# T11-MIDITheremin.net
KiCad netlist of a schematic drawn in EAGLE
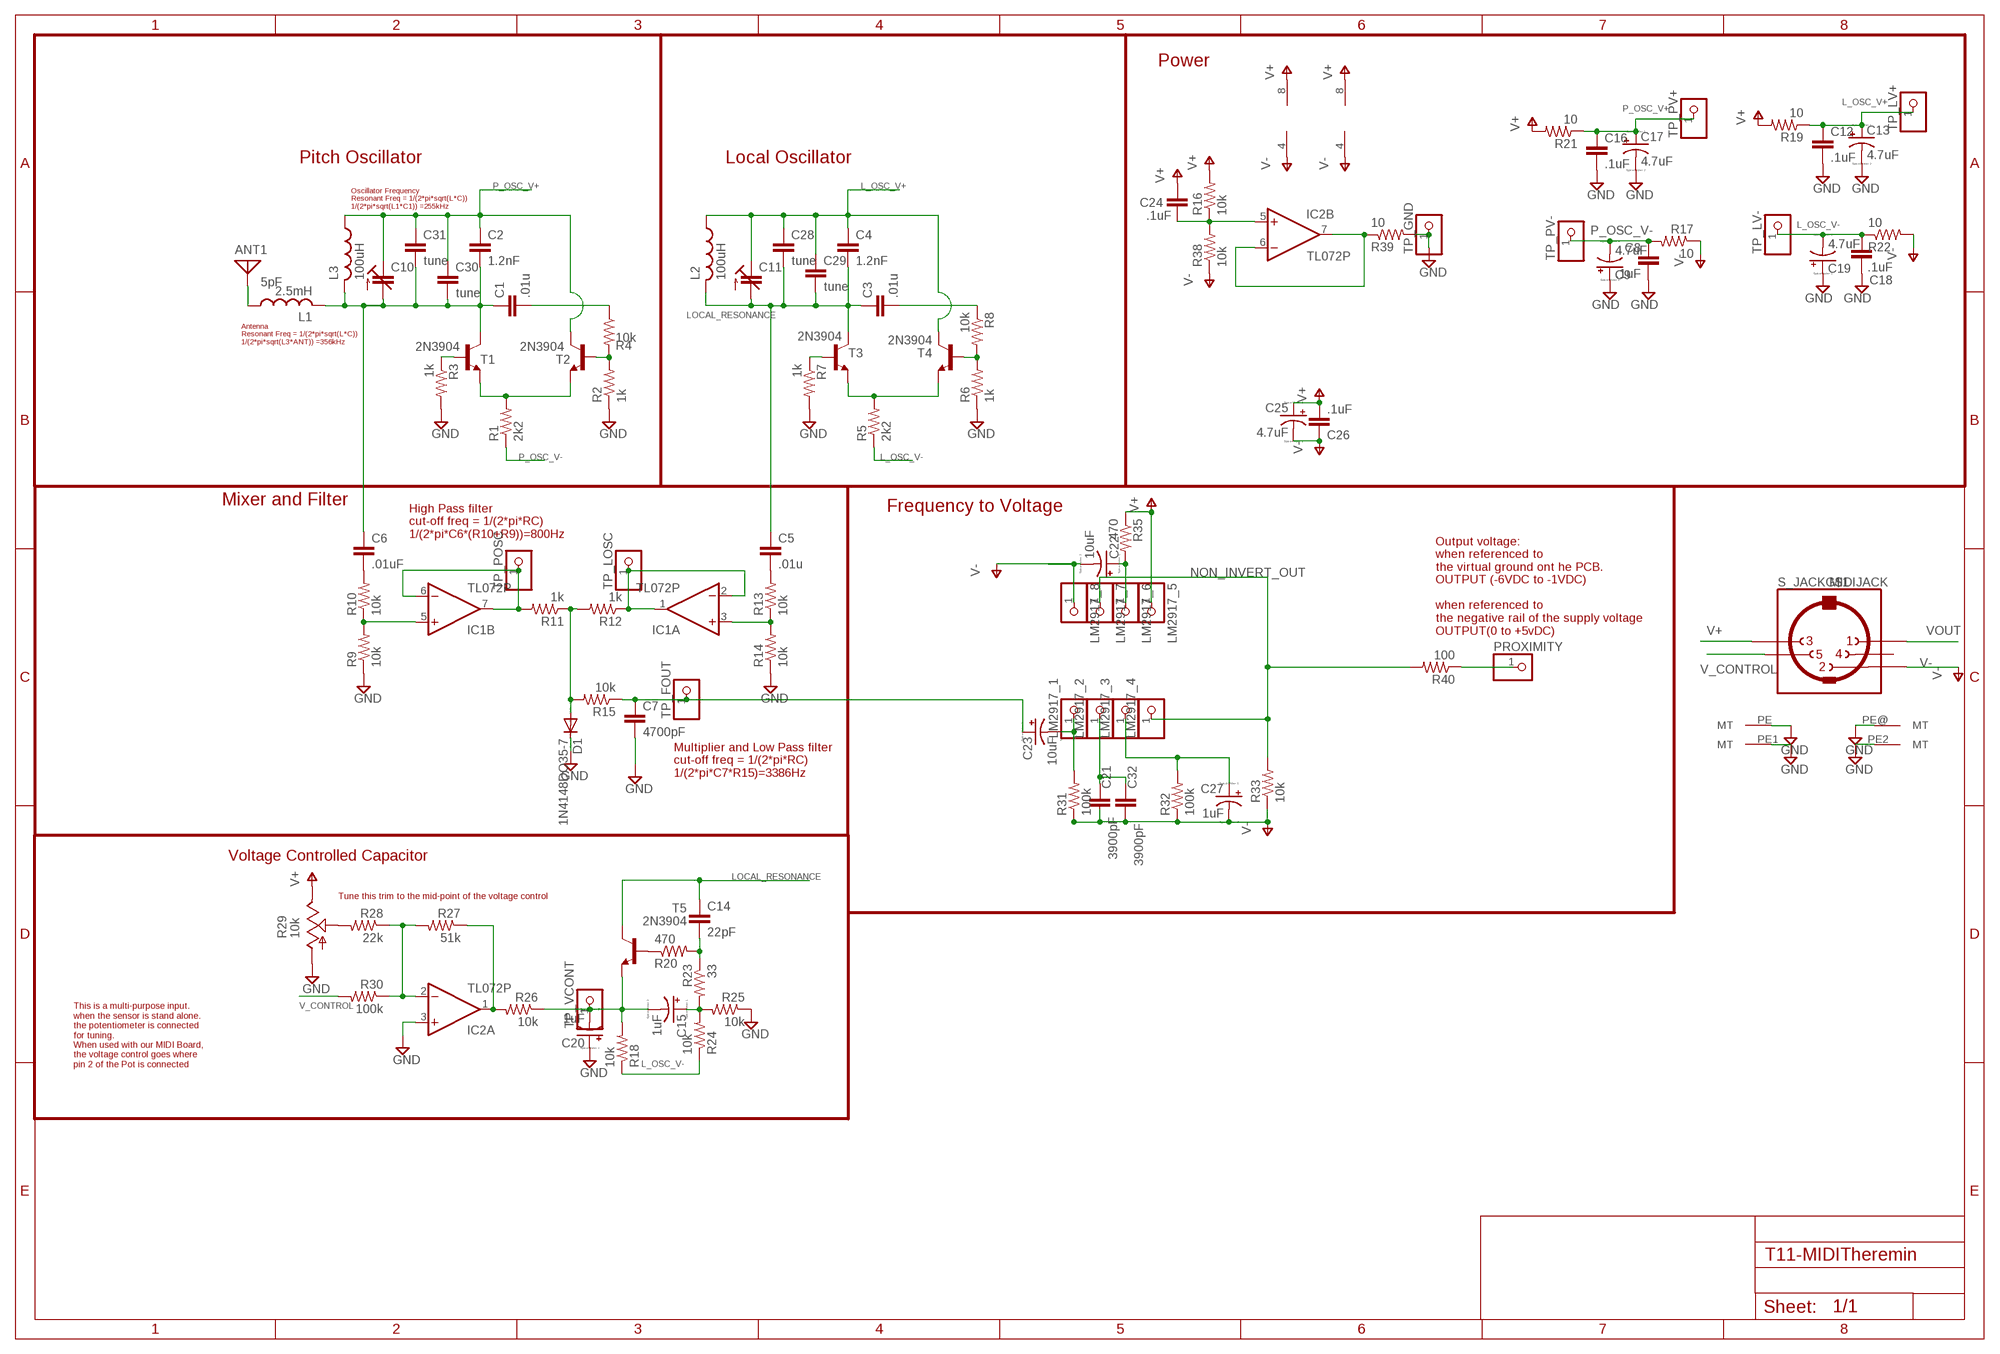
[diagram p0: schematic, sheet 1]

(export (version "E")
  (design (tool "Eeschema 10.0.6"))
  (components
    (comp (ref "ANT1")
      (value "5pF")
      (footprint "eagle-import:PAD-01")
      (libsource (lib "eagle-import") (part "ANTENNA"))
    )
    (comp (ref "C1")
      (value ".01u")
      (footprint "eagle-import:C050-025X075")
      (libsource (lib "eagle-import") (part "C-EU050-025X075"))
    )
    (comp (ref "C2")
      (value "1.2nF")
      (footprint "eagle-import:C050-025X075")
      (libsource (lib "eagle-import") (part "C-EU050-025X075"))
    )
    (comp (ref "C3")
      (value ".01u")
      (footprint "eagle-import:C050-025X075")
      (libsource (lib "eagle-import") (part "C-EU050-025X075"))
    )
    (comp (ref "C4")
      (value "1.2nF")
      (footprint "eagle-import:C050-025X075")
      (libsource (lib "eagle-import") (part "C-EU050-025X075"))
    )
    (comp (ref "C5")
      (value ".01u")
      (footprint "eagle-import:C050-025X075")
      (libsource (lib "eagle-import") (part "C-EU050-025X075"))
    )
    (comp (ref "C6")
      (value ".01uF")
      (footprint "eagle-import:C050-025X075")
      (libsource (lib "eagle-import") (part "C-EU050-025X075"))
    )
    (comp (ref "C7")
      (value "4700pF")
      (footprint "eagle-import:C050-025X075")
      (libsource (lib "eagle-import") (part "C-EU050-025X075"))
    )
    (comp (ref "C8")
      (value ".1uF")
      (footprint "eagle-import:C050-025X075")
      (libsource (lib "eagle-import") (part "C-EU050-025X075"))
    )
    (comp (ref "C9")
      (value "4.7uF")
      (footprint "eagle-import:E2,5-7")
      (libsource (lib "eagle-import") (part "CPOL-USE2.5-7"))
    )
    (comp (ref "C10")
      (value "C-TRIMM3040.427")
      (footprint "eagle-import:CTRIM3040.427")
      (libsource (lib "eagle-import") (part "C-TRIMM3040.427"))
    )
    (comp (ref "C11")
      (value "C-TRIMM3040.427")
      (footprint "eagle-import:CTRIM3040.427")
      (libsource (lib "eagle-import") (part "C-TRIMM3040.427"))
    )
    (comp (ref "C12")
      (value ".1uF")
      (footprint "eagle-import:C050-025X075")
      (libsource (lib "eagle-import") (part "C-EU050-025X075"))
    )
    (comp (ref "C13")
      (value "4.7uF")
      (footprint "eagle-import:E2,5-7")
      (libsource (lib "eagle-import") (part "CPOL-USE2.5-7"))
    )
    (comp (ref "C14")
      (value "22pF")
      (footprint "eagle-import:C050-025X075")
      (libsource (lib "eagle-import") (part "C-EU050-025X075"))
    )
    (comp (ref "C15")
      (value "1uF")
      (footprint "eagle-import:E2,5-7")
      (libsource (lib "eagle-import") (part "CPOL-USE2.5-7"))
    )
    (comp (ref "C16")
      (value ".1uF")
      (footprint "eagle-import:C050-025X075")
      (libsource (lib "eagle-import") (part "C-EU050-025X075"))
    )
    (comp (ref "C17")
      (value "4.7uF")
      (footprint "eagle-import:E2,5-7")
      (libsource (lib "eagle-import") (part "CPOL-USE2.5-7"))
    )
    (comp (ref "C18")
      (value ".1uF")
      (footprint "eagle-import:C050-025X075")
      (libsource (lib "eagle-import") (part "C-EU050-025X075"))
    )
    (comp (ref "C19")
      (value "4.7uF")
      (footprint "eagle-import:E2,5-7")
      (libsource (lib "eagle-import") (part "CPOL-USE2.5-7"))
    )
    (comp (ref "C20")
      (value "1uF")
      (footprint "eagle-import:E2,5-7")
      (libsource (lib "eagle-import") (part "CPOL-USE2.5-7"))
    )
    (comp (ref "C21")
      (value "3900pF")
      (footprint "eagle-import:C050-025X075")
      (libsource (lib "eagle-import") (part "C-EU050-025X075"))
    )
    (comp (ref "C22")
      (value "10uF")
      (footprint "eagle-import:E2,5-7")
      (libsource (lib "eagle-import") (part "CPOL-USE2.5-7"))
    )
    (comp (ref "C23")
      (value "10uF")
      (footprint "eagle-import:E2,5-7")
      (libsource (lib "eagle-import") (part "CPOL-USE2.5-7"))
    )
    (comp (ref "C24")
      (value ".1uF")
      (footprint "eagle-import:C050-025X075")
      (libsource (lib "eagle-import") (part "C-EU050-025X075"))
    )
    (comp (ref "C25")
      (value "4.7uF")
      (footprint "eagle-import:E2,5-7")
      (libsource (lib "eagle-import") (part "CPOL-USE2.5-7"))
    )
    (comp (ref "C26")
      (value ".1uF")
      (footprint "eagle-import:C050-025X075")
      (libsource (lib "eagle-import") (part "C-EU050-025X075"))
    )
    (comp (ref "C27")
      (value "1uF")
      (footprint "eagle-import:E2,5-7")
      (libsource (lib "eagle-import") (part "CPOL-USE2.5-7"))
    )
    (comp (ref "C28")
      (value "tune")
      (footprint "eagle-import:C050-025X075")
      (libsource (lib "eagle-import") (part "C-EU050-025X075"))
    )
    (comp (ref "C29")
      (value "tune")
      (footprint "eagle-import:C050-025X075")
      (libsource (lib "eagle-import") (part "C-EU050-025X075"))
    )
    (comp (ref "C30")
      (value "tune")
      (footprint "eagle-import:C050-025X075")
      (libsource (lib "eagle-import") (part "C-EU050-025X075"))
    )
    (comp (ref "C31")
      (value "tune")
      (footprint "eagle-import:C050-025X075")
      (libsource (lib "eagle-import") (part "C-EU050-025X075"))
    )
    (comp (ref "C32")
      (value "3900pF")
      (footprint "eagle-import:C050-025X075")
      (libsource (lib "eagle-import") (part "C-EU050-025X075"))
    )
    (comp (ref "D1")
      (value "1N4148DO35-7")
      (footprint "eagle-import:DO35-7")
      (libsource (lib "eagle-import") (part "1N4148DO35-7"))
    )
    (comp (ref "IC1")
      (value "TL072P")
      (footprint "eagle-import:DIL08")
      (libsource (lib "eagle-import") (part "TL072P"))
    )
    (comp (ref "IC2")
      (value "TL072P")
      (footprint "eagle-import:DIL08")
      (libsource (lib "eagle-import") (part "TL072P"))
    )
    (comp (ref "L1")
      (value "2.5mH")
      (footprint "eagle-import:0207_5V")
      (libsource (lib "eagle-import") (part "L-US0207/5V"))
    )
    (comp (ref "L2")
      (value "100uH")
      (footprint "eagle-import:0207_5V")
      (libsource (lib "eagle-import") (part "L-US0207/5V"))
    )
    (comp (ref "L3")
      (value "100uH")
      (footprint "eagle-import:0207_5V")
      (libsource (lib "eagle-import") (part "L-US0207/5V"))
    )
    (comp (ref "LM2917_1")
      (value "PINHD-1X1")
      (footprint "eagle-import:1X01")
      (libsource (lib "eagle-import") (part "PINHD-1X1"))
    )
    (comp (ref "LM2917_2")
      (value "PINHD-1X1")
      (footprint "eagle-import:1X01")
      (libsource (lib "eagle-import") (part "PINHD-1X1"))
    )
    (comp (ref "LM2917_3")
      (value "PINHD-1X1")
      (footprint "eagle-import:1X01")
      (libsource (lib "eagle-import") (part "PINHD-1X1"))
    )
    (comp (ref "LM2917_4")
      (value "PINHD-1X1")
      (footprint "eagle-import:1X01")
      (libsource (lib "eagle-import") (part "PINHD-1X1"))
    )
    (comp (ref "LM2917_5")
      (value "PINHD-1X1")
      (footprint "eagle-import:1X01")
      (libsource (lib "eagle-import") (part "PINHD-1X1"))
    )
    (comp (ref "LM2917_6")
      (value "PINHD-1X1")
      (footprint "eagle-import:1X01")
      (libsource (lib "eagle-import") (part "PINHD-1X1"))
    )
    (comp (ref "LM2917_7")
      (value "PINHD-1X1")
      (footprint "eagle-import:1X01")
      (libsource (lib "eagle-import") (part "PINHD-1X1"))
    )
    (comp (ref "LM2917_8")
      (value "PINHD-1X1")
      (footprint "eagle-import:1X01")
      (libsource (lib "eagle-import") (part "PINHD-1X1"))
    )
    (comp (ref "PROXIMITY")
      (value "PINHD-1X1")
      (footprint "eagle-import:1X01")
      (libsource (lib "eagle-import") (part "PINHD-1X1"))
    )
    (comp (ref "R1")
      (value "2k2")
      (footprint "eagle-import:0411V")
      (libsource (lib "eagle-import") (part "resistor_R-US_0411/3V"))
    )
    (comp (ref "R2")
      (value "1k")
      (footprint "eagle-import:0411V")
      (libsource (lib "eagle-import") (part "resistor_R-US_0411/3V"))
    )
    (comp (ref "R3")
      (value "1k")
      (footprint "eagle-import:0411V")
      (libsource (lib "eagle-import") (part "resistor_R-US_0411/3V"))
    )
    (comp (ref "R4")
      (value "10k")
      (footprint "eagle-import:0411V")
      (libsource (lib "eagle-import") (part "resistor_R-US_0411/3V"))
    )
    (comp (ref "R5")
      (value "2k2")
      (footprint "eagle-import:0411V")
      (libsource (lib "eagle-import") (part "resistor_R-US_0411/3V"))
    )
    (comp (ref "R6")
      (value "1k")
      (footprint "eagle-import:0411V")
      (libsource (lib "eagle-import") (part "resistor_R-US_0411/3V"))
    )
    (comp (ref "R7")
      (value "1k")
      (footprint "eagle-import:0411V")
      (libsource (lib "eagle-import") (part "resistor_R-US_0411/3V"))
    )
    (comp (ref "R8")
      (value "10k")
      (footprint "eagle-import:0411V")
      (libsource (lib "eagle-import") (part "resistor_R-US_0411/3V"))
    )
    (comp (ref "R9")
      (value "10k")
      (footprint "eagle-import:0411V")
      (libsource (lib "eagle-import") (part "resistor_R-US_0411/3V"))
    )
    (comp (ref "R10")
      (value "10k")
      (footprint "eagle-import:0411V")
      (libsource (lib "eagle-import") (part "resistor_R-US_0411/3V"))
    )
    (comp (ref "R11")
      (value "1k")
      (footprint "eagle-import:0411V")
      (libsource (lib "eagle-import") (part "resistor_R-US_0411/3V"))
    )
    (comp (ref "R12")
      (value "1k")
      (footprint "eagle-import:0411V")
      (libsource (lib "eagle-import") (part "resistor_R-US_0411/3V"))
    )
    (comp (ref "R13")
      (value "10k")
      (footprint "eagle-import:0411V")
      (libsource (lib "eagle-import") (part "resistor_R-US_0411/3V"))
    )
    (comp (ref "R14")
      (value "10k")
      (footprint "eagle-import:0411V")
      (libsource (lib "eagle-import") (part "resistor_R-US_0411/3V"))
    )
    (comp (ref "R15")
      (value "10k")
      (footprint "eagle-import:0411V")
      (libsource (lib "eagle-import") (part "resistor_R-US_0411/3V"))
    )
    (comp (ref "R16")
      (value "10k")
      (footprint "eagle-import:0411V")
      (libsource (lib "eagle-import") (part "resistor_R-US_0411/3V"))
    )
    (comp (ref "R17")
      (value "10")
      (footprint "eagle-import:0411V")
      (libsource (lib "eagle-import") (part "resistor_R-US_0411/3V"))
    )
    (comp (ref "R18")
      (value "10k")
      (footprint "eagle-import:0411V")
      (libsource (lib "eagle-import") (part "resistor_R-US_0411/3V"))
    )
    (comp (ref "R19")
      (value "10")
      (footprint "eagle-import:0411V")
      (libsource (lib "eagle-import") (part "resistor_R-US_0411/3V"))
    )
    (comp (ref "R20")
      (value "470")
      (footprint "eagle-import:0411V")
      (libsource (lib "eagle-import") (part "resistor_R-US_0411/3V"))
    )
    (comp (ref "R21")
      (value "10")
      (footprint "eagle-import:0411V")
      (libsource (lib "eagle-import") (part "resistor_R-US_0411/3V"))
    )
    (comp (ref "R22")
      (value "10")
      (footprint "eagle-import:0411V")
      (libsource (lib "eagle-import") (part "resistor_R-US_0411/3V"))
    )
    (comp (ref "R23")
      (value "33")
      (footprint "eagle-import:0411V")
      (libsource (lib "eagle-import") (part "resistor_R-US_0411/3V"))
    )
    (comp (ref "R24")
      (value "10k")
      (footprint "eagle-import:0411V")
      (libsource (lib "eagle-import") (part "resistor_R-US_0411/3V"))
    )
    (comp (ref "R25")
      (value "10k")
      (footprint "eagle-import:0411V")
      (libsource (lib "eagle-import") (part "resistor_R-US_0411/3V"))
    )
    (comp (ref "R26")
      (value "10k")
      (footprint "eagle-import:0411V")
      (libsource (lib "eagle-import") (part "resistor_R-US_0411/3V"))
    )
    (comp (ref "R27")
      (value "51k")
      (footprint "eagle-import:0411V")
      (libsource (lib "eagle-import") (part "resistor_R-US_0411/3V"))
    )
    (comp (ref "R28")
      (value "22k")
      (footprint "eagle-import:0411V")
      (libsource (lib "eagle-import") (part "resistor_R-US_0411/3V"))
    )
    (comp (ref "R29")
      (value "10k")
      (footprint "eagle-import:B64Y")
      (libsource (lib "eagle-import") (part "TRIM_US-B64Y"))
    )
    (comp (ref "R30")
      (value "100k")
      (footprint "eagle-import:0411V")
      (libsource (lib "eagle-import") (part "resistor_R-US_0411/3V"))
    )
    (comp (ref "R31")
      (value "100k")
      (footprint "eagle-import:0411V")
      (libsource (lib "eagle-import") (part "R-US_0411/3V"))
    )
    (comp (ref "R32")
      (value "100k")
      (footprint "eagle-import:0411V")
      (libsource (lib "eagle-import") (part "R-US_0411/3V"))
    )
    (comp (ref "R33")
      (value "10k")
      (footprint "eagle-import:0411V")
      (libsource (lib "eagle-import") (part "R-US_0411/3V"))
    )
    (comp (ref "R35")
      (value "470")
      (footprint "eagle-import:0411V")
      (libsource (lib "eagle-import") (part "R-US_0411/3V"))
    )
    (comp (ref "R38")
      (value "10k")
      (footprint "eagle-import:0411V")
      (libsource (lib "eagle-import") (part "resistor_R-US_0411/3V"))
    )
    (comp (ref "R39")
      (value "10")
      (footprint "eagle-import:0411V")
      (libsource (lib "eagle-import") (part "resistor_R-US_0411/3V"))
    )
    (comp (ref "R40")
      (value "100")
      (footprint "eagle-import:0411V")
      (libsource (lib "eagle-import") (part "R-US_0411/3V"))
    )
    (comp (ref "S_JACK")
      (value "MIDIJACK")
      (footprint "eagle-import:CP-2350")
      (libsource (lib "eagle-import") (part "MIDIJACK"))
    )
    (comp (ref "T1")
      (value "2N3904")
      (footprint "eagle-import:TO92")
      (libsource (lib "eagle-import") (part "2N3904"))
    )
    (comp (ref "T2")
      (value "2N3904")
      (footprint "eagle-import:TO92")
      (libsource (lib "eagle-import") (part "2N3904"))
    )
    (comp (ref "T3")
      (value "2N3904")
      (footprint "eagle-import:TO92")
      (libsource (lib "eagle-import") (part "2N3904"))
    )
    (comp (ref "T4")
      (value "2N3904")
      (footprint "eagle-import:TO92")
      (libsource (lib "eagle-import") (part "2N3904"))
    )
    (comp (ref "T5")
      (value "2N3904")
      (footprint "eagle-import:TO92")
      (libsource (lib "eagle-import") (part "2N3904"))
    )
    (comp (ref "TP_FOUT")
      (value "PINHD-1X1")
      (footprint "eagle-import:1X01")
      (libsource (lib "eagle-import") (part "PINHD-1X1"))
    )
    (comp (ref "TP_GND")
      (value "PINHD-1X1")
      (footprint "eagle-import:1X01")
      (libsource (lib "eagle-import") (part "PINHD-1X1"))
    )
    (comp (ref "TP_LOSC")
      (value "PINHD-1X1")
      (footprint "eagle-import:1X01")
      (libsource (lib "eagle-import") (part "PINHD-1X1"))
    )
    (comp (ref "TP_LV+")
      (value "PINHD-1X1")
      (footprint "eagle-import:1X01")
      (libsource (lib "eagle-import") (part "PINHD-1X1"))
    )
    (comp (ref "TP_LV-")
      (value "PINHD-1X1")
      (footprint "eagle-import:1X01")
      (libsource (lib "eagle-import") (part "PINHD-1X1"))
    )
    (comp (ref "TP_POSC")
      (value "PINHD-1X1")
      (footprint "eagle-import:1X01")
      (libsource (lib "eagle-import") (part "PINHD-1X1"))
    )
    (comp (ref "TP_PV+")
      (value "PINHD-1X1")
      (footprint "eagle-import:1X01")
      (libsource (lib "eagle-import") (part "PINHD-1X1"))
    )
    (comp (ref "TP_PV-")
      (value "PINHD-1X1")
      (footprint "eagle-import:1X01")
      (libsource (lib "eagle-import") (part "PINHD-1X1"))
    )
    (comp (ref "TP_VCONT")
      (value "PINHD-1X1")
      (footprint "eagle-import:1X01")
      (libsource (lib "eagle-import") (part "PINHD-1X1"))
    )
  )
  (nets
    (net (code "1") (name "/LOCAL_RESONANCE") (class "Default")
      (node (ref "C11") (pin "2") (pinfunction "A_2") (pintype "passive"))
      (node (ref "C14") (pin "1") (pinfunction "1_1") (pintype "passive"))
      (node (ref "C28") (pin "2") (pinfunction "2_2") (pintype "passive"))
      (node (ref "C29") (pin "2") (pinfunction "2_2") (pintype "passive"))
      (node (ref "C3") (pin "1") (pinfunction "1_1") (pintype "passive"))
      (node (ref "C4") (pin "2") (pinfunction "2_2") (pintype "passive"))
      (node (ref "C5") (pin "1") (pinfunction "1_1") (pintype "passive"))
      (node (ref "L2") (pin "2") (pinfunction "2_2") (pintype "passive"))
      (node (ref "T3") (pin "1") (pinfunction "C_1") (pintype "passive"))
      (node (ref "T5") (pin "1") (pinfunction "C_1") (pintype "passive"))
    )
    (net (code "2") (name "/L_OSC_V+") (class "Default")
      (node (ref "C11") (pin "1A") (pinfunction "E_1A") (pintype "passive"))
      (node (ref "C12") (pin "1") (pinfunction "1_1") (pintype "passive"))
      (node (ref "C13") (pin "+") (pinfunction "+_+") (pintype "passive"))
      (node (ref "C28") (pin "1") (pinfunction "1_1") (pintype "passive"))
      (node (ref "C29") (pin "1") (pinfunction "1_1") (pintype "passive"))
      (node (ref "C4") (pin "1") (pinfunction "1_1") (pintype "passive"))
      (node (ref "L2") (pin "1") (pinfunction "1_1") (pintype "passive"))
      (node (ref "R19") (pin "1") (pinfunction "1_1") (pintype "passive"))
      (node (ref "T4") (pin "1") (pinfunction "C_1") (pintype "passive"))
      (node (ref "TP_LV+") (pin "1") (pinfunction "1_1") (pintype "passive"))
    )
    (net (code "3") (name "/L_OSC_V-") (class "Default")
      (node (ref "C18") (pin "1") (pinfunction "1_1") (pintype "passive"))
      (node (ref "C19") (pin "-") (pinfunction "-_-") (pintype "passive"))
      (node (ref "R18") (pin "1") (pinfunction "1_1") (pintype "passive"))
      (node (ref "R22") (pin "1") (pinfunction "1_1") (pintype "passive"))
      (node (ref "R24") (pin "1") (pinfunction "1_1") (pintype "passive"))
      (node (ref "R5") (pin "1") (pinfunction "1_1") (pintype "passive"))
      (node (ref "TP_LV-") (pin "1") (pinfunction "1_1") (pintype "passive"))
    )
    (net (code "4") (name "/NON_INVERT_OUT") (class "Default")
      (node (ref "LM2917_4") (pin "1") (pinfunction "1_1") (pintype "passive"))
      (node (ref "LM2917_7") (pin "1") (pinfunction "1_1") (pintype "passive"))
      (node (ref "R33") (pin "2") (pinfunction "2_2") (pintype "passive"))
      (node (ref "R40") (pin "2") (pinfunction "2_2") (pintype "passive"))
    )
    (net (code "5") (name "/P_OSC_V+") (class "Default")
      (node (ref "C10") (pin "1A") (pinfunction "E_1A") (pintype "passive"))
      (node (ref "C16") (pin "1") (pinfunction "1_1") (pintype "passive"))
      (node (ref "C17") (pin "+") (pinfunction "+_+") (pintype "passive"))
      (node (ref "C2") (pin "1") (pinfunction "1_1") (pintype "passive"))
      (node (ref "C30") (pin "1") (pinfunction "1_1") (pintype "passive"))
      (node (ref "C31") (pin "1") (pinfunction "1_1") (pintype "passive"))
      (node (ref "L3") (pin "1") (pinfunction "1_1") (pintype "passive"))
      (node (ref "R21") (pin "1") (pinfunction "1_1") (pintype "passive"))
      (node (ref "T2") (pin "1") (pinfunction "C_1") (pintype "passive"))
      (node (ref "TP_PV+") (pin "1") (pinfunction "1_1") (pintype "passive"))
    )
    (net (code "6") (name "/P_OSC_V-") (class "Default")
      (node (ref "C8") (pin "1") (pinfunction "1_1") (pintype "passive"))
      (node (ref "C9") (pin "-") (pinfunction "-_-") (pintype "passive"))
      (node (ref "R1") (pin "1") (pinfunction "1_1") (pintype "passive"))
      (node (ref "R17") (pin "2") (pinfunction "2_2") (pintype "passive"))
      (node (ref "TP_PV-") (pin "1") (pinfunction "1_1") (pintype "passive"))
    )
    (net (code "7") (name "/VOUT") (class "Default")
      (node (ref "PROXIMITY") (pin "1") (pinfunction "1_1") (pintype "passive"))
      (node (ref "R40") (pin "1") (pinfunction "1_1") (pintype "passive"))
      (node (ref "S_JACK") (pin "1") (pinfunction "1_1") (pintype "passive"))
    )
    (net (code "8") (name "/V_CONTROL") (class "Default")
      (node (ref "R30") (pin "2") (pinfunction "2_2") (pintype "passive"))
      (node (ref "S_JACK") (pin "5") (pinfunction "5_5") (pintype "passive"))
    )
    (net (code "9") (name "GND") (class "Default")
      (node (ref "C12") (pin "2") (pinfunction "2_2") (pintype "passive"))
      (node (ref "C13") (pin "-") (pinfunction "-_-") (pintype "passive"))
      (node (ref "C16") (pin "2") (pinfunction "2_2") (pintype "passive"))
      (node (ref "C17") (pin "-") (pinfunction "-_-") (pintype "passive"))
      (node (ref "C18") (pin "2") (pinfunction "2_2") (pintype "passive"))
      (node (ref "C19") (pin "+") (pinfunction "+_+") (pintype "passive"))
      (node (ref "C20") (pin "+") (pinfunction "+_+") (pintype "passive"))
      (node (ref "C7") (pin "2") (pinfunction "2_2") (pintype "passive"))
      (node (ref "C8") (pin "2") (pinfunction "2_2") (pintype "passive"))
      (node (ref "C9") (pin "+") (pinfunction "+_+") (pintype "passive"))
      (node (ref "D1") (pin "C") (pinfunction "C_C") (pintype "passive"))
      (node (ref "IC2") (pin "3") (pinfunction "+IN_3") (pintype "input"))
      (node (ref "R14") (pin "1") (pinfunction "1_1") (pintype "passive"))
      (node (ref "R2") (pin "1") (pinfunction "1_1") (pintype "passive"))
      (node (ref "R25") (pin "1") (pinfunction "1_1") (pintype "passive"))
      (node (ref "R29") (pin "A") (pinfunction "A_A") (pintype "passive"))
      (node (ref "R3") (pin "2") (pinfunction "2_2") (pintype "passive"))
      (node (ref "R39") (pin "2") (pinfunction "2_2") (pintype "passive"))
      (node (ref "R6") (pin "1") (pinfunction "1_1") (pintype "passive"))
      (node (ref "R7") (pin "2") (pinfunction "2_2") (pintype "passive"))
      (node (ref "R9") (pin "1") (pinfunction "1_1") (pintype "passive"))
      (node (ref "S_JACK") (pin "PE") (pinfunction "MT_PE") (pintype "passive"))
      (node (ref "S_JACK") (pin "PE1") (pinfunction "MT_PE1") (pintype "passive"))
      (node (ref "S_JACK") (pin "PE2") (pinfunction "MT_PE2") (pintype "passive"))
      (node (ref "S_JACK") (pin "PE@") (pinfunction "MT_PE@") (pintype "passive"))
      (node (ref "TP_GND") (pin "1") (pinfunction "1_1") (pintype "passive"))
    )
    (net (code "10") (name "Net-(ANT1-Pad1)") (class "Default")
      (node (ref "ANT1") (pin "1") (pinfunction "1_1") (pintype "output"))
      (node (ref "L1") (pin "1") (pinfunction "1_1") (pintype "passive"))
    )
    (net (code "11") (name "Net-(C1-Pad2)") (class "Default")
      (node (ref "C1") (pin "2") (pinfunction "2_2") (pintype "passive"))
      (node (ref "R4") (pin "1") (pinfunction "1_1") (pintype "passive"))
    )
    (net (code "12") (name "Net-(C3-Pad2)") (class "Default")
      (node (ref "C3") (pin "2") (pinfunction "2_2") (pintype "passive"))
      (node (ref "R8") (pin "1") (pinfunction "1_1") (pintype "passive"))
    )
    (net (code "13") (name "Net-(C5-Pad2)") (class "Default")
      (node (ref "C5") (pin "2") (pinfunction "2_2") (pintype "passive"))
      (node (ref "R13") (pin "2") (pinfunction "2_2") (pintype "passive"))
    )
    (net (code "14") (name "Net-(C6-Pad2)") (class "Default")
      (node (ref "C6") (pin "2") (pinfunction "2_2") (pintype "passive"))
      (node (ref "R10") (pin "2") (pinfunction "2_2") (pintype "passive"))
    )
    (net (code "15") (name "Net-(C10-A)") (class "Default")
      (node (ref "C1") (pin "1") (pinfunction "1_1") (pintype "passive"))
      (node (ref "C10") (pin "2") (pinfunction "A_2") (pintype "passive"))
      (node (ref "C2") (pin "2") (pinfunction "2_2") (pintype "passive"))
      (node (ref "C30") (pin "2") (pinfunction "2_2") (pintype "passive"))
      (node (ref "C31") (pin "2") (pinfunction "2_2") (pintype "passive"))
      (node (ref "C6") (pin "1") (pinfunction "1_1") (pintype "passive"))
      (node (ref "L1") (pin "2") (pinfunction "2_2") (pintype "passive"))
      (node (ref "L3") (pin "2") (pinfunction "2_2") (pintype "passive"))
      (node (ref "T1") (pin "1") (pinfunction "C_1") (pintype "passive"))
    )
    (net (code "16") (name "Net-(C14-Pad2)") (class "Default")
      (node (ref "C14") (pin "2") (pinfunction "2_2") (pintype "passive"))
      (node (ref "R20") (pin "2") (pinfunction "2_2") (pintype "passive"))
      (node (ref "R23") (pin "1") (pinfunction "1_1") (pintype "passive"))
    )
    (net (code "17") (name "Net-(C15-Pad+)") (class "Default")
      (node (ref "C15") (pin "+") (pinfunction "+_+") (pintype "passive"))
      (node (ref "R23") (pin "2") (pinfunction "2_2") (pintype "passive"))
      (node (ref "R24") (pin "2") (pinfunction "2_2") (pintype "passive"))
      (node (ref "R25") (pin "2") (pinfunction "2_2") (pintype "passive"))
    )
    (net (code "18") (name "Net-(C21-Pad1)") (class "Default")
      (node (ref "C21") (pin "1") (pinfunction "1_1") (pintype "passive"))
      (node (ref "C32") (pin "1") (pinfunction "1_1") (pintype "passive"))
      (node (ref "LM2917_2") (pin "1") (pinfunction "1_1") (pintype "passive"))
    )
    (net (code "19") (name "Net-(C22-Pad+)") (class "Default")
      (node (ref "C22") (pin "+") (pinfunction "+_+") (pintype "passive"))
      (node (ref "LM2917_6") (pin "1") (pinfunction "1_1") (pintype "passive"))
      (node (ref "R35") (pin "2") (pinfunction "2_2") (pintype "passive"))
    )
    (net (code "20") (name "Net-(C23-Pad+)") (class "Default")
      (node (ref "C23") (pin "+") (pinfunction "+_+") (pintype "passive"))
      (node (ref "C7") (pin "1") (pinfunction "1_1") (pintype "passive"))
      (node (ref "R15") (pin "1") (pinfunction "1_1") (pintype "passive"))
      (node (ref "TP_FOUT") (pin "1") (pinfunction "1_1") (pintype "passive"))
    )
    (net (code "21") (name "Net-(C23-Pad-)") (class "Default")
      (node (ref "C23") (pin "-") (pinfunction "-_-") (pintype "passive"))
      (node (ref "LM2917_1") (pin "1") (pinfunction "1_1") (pintype "passive"))
      (node (ref "R31") (pin "2") (pinfunction "2_2") (pintype "passive"))
    )
    (net (code "22") (name "Net-(C27-Pad+)") (class "Default")
      (node (ref "C27") (pin "+") (pinfunction "+_+") (pintype "passive"))
      (node (ref "LM2917_3") (pin "1") (pinfunction "1_1") (pintype "passive"))
      (node (ref "R32") (pin "2") (pinfunction "2_2") (pintype "passive"))
    )
    (net (code "23") (name "Net-(D1-PadA)") (class "Default")
      (node (ref "D1") (pin "A") (pinfunction "A_A") (pintype "passive"))
      (node (ref "R11") (pin "1") (pinfunction "1_1") (pintype "passive"))
      (node (ref "R12") (pin "2") (pinfunction "2_2") (pintype "passive"))
      (node (ref "R15") (pin "2") (pinfunction "2_2") (pintype "passive"))
    )
    (net (code "24") (name "Net-(IC1A-+IN)") (class "Default")
      (node (ref "IC1") (pin "3") (pinfunction "+IN_3") (pintype "input"))
      (node (ref "R13") (pin "1") (pinfunction "1_1") (pintype "passive"))
      (node (ref "R14") (pin "2") (pinfunction "2_2") (pintype "passive"))
    )
    (net (code "25") (name "Net-(IC1A--IN)") (class "Default")
      (node (ref "IC1") (pin "1") (pinfunction "OUT_1") (pintype "output"))
      (node (ref "IC1") (pin "2") (pinfunction "-IN_2") (pintype "input"))
      (node (ref "R12") (pin "1") (pinfunction "1_1") (pintype "passive"))
      (node (ref "TP_LOSC") (pin "1") (pinfunction "1_1") (pintype "passive"))
    )
    (net (code "26") (name "Net-(IC1B-+IN)") (class "Default")
      (node (ref "IC1") (pin "5") (pinfunction "+IN_5") (pintype "input"))
      (node (ref "R10") (pin "1") (pinfunction "1_1") (pintype "passive"))
      (node (ref "R9") (pin "2") (pinfunction "2_2") (pintype "passive"))
    )
    (net (code "27") (name "Net-(IC1B--IN)") (class "Default")
      (node (ref "IC1") (pin "6") (pinfunction "-IN_6") (pintype "input"))
      (node (ref "IC1") (pin "7") (pinfunction "OUT_7") (pintype "output"))
      (node (ref "R11") (pin "2") (pinfunction "2_2") (pintype "passive"))
      (node (ref "TP_POSC") (pin "1") (pinfunction "1_1") (pintype "passive"))
    )
    (net (code "28") (name "Net-(IC2A--IN)") (class "Default")
      (node (ref "IC2") (pin "2") (pinfunction "-IN_2") (pintype "input"))
      (node (ref "R27") (pin "2") (pinfunction "2_2") (pintype "passive"))
      (node (ref "R28") (pin "1") (pinfunction "1_1") (pintype "passive"))
      (node (ref "R30") (pin "1") (pinfunction "1_1") (pintype "passive"))
    )
    (net (code "29") (name "Net-(IC2A-OUT)") (class "Default")
      (node (ref "IC2") (pin "1") (pinfunction "OUT_1") (pintype "output"))
      (node (ref "R26") (pin "2") (pinfunction "2_2") (pintype "passive"))
      (node (ref "R27") (pin "1") (pinfunction "1_1") (pintype "passive"))
    )
    (net (code "30") (name "Net-(IC2B-+IN)") (class "Default")
      (node (ref "C24") (pin "2") (pinfunction "2_2") (pintype "passive"))
      (node (ref "IC2") (pin "5") (pinfunction "+IN_5") (pintype "input"))
      (node (ref "R16") (pin "1") (pinfunction "1_1") (pintype "passive"))
      (node (ref "R38") (pin "2") (pinfunction "2_2") (pintype "passive"))
    )
    (net (code "31") (name "Net-(IC2B--IN)") (class "Default")
      (node (ref "IC2") (pin "6") (pinfunction "-IN_6") (pintype "input"))
      (node (ref "IC2") (pin "7") (pinfunction "OUT_7") (pintype "output"))
      (node (ref "R39") (pin "1") (pinfunction "1_1") (pintype "passive"))
    )
    (net (code "32") (name "Net-(R28-Pad2)") (class "Default")
      (node (ref "R28") (pin "2") (pinfunction "2_2") (pintype "passive"))
      (node (ref "R29") (pin "S") (pinfunction "S_S") (pintype "passive"))
    )
    (net (code "33") (name "Net-(T1-B)") (class "Default")
      (node (ref "R3") (pin "1") (pinfunction "1_1") (pintype "passive"))
      (node (ref "T1") (pin "2") (pinfunction "B_2") (pintype "passive"))
    )
    (net (code "34") (name "Net-(T1-E)") (class "Default")
      (node (ref "R1") (pin "2") (pinfunction "2_2") (pintype "passive"))
      (node (ref "T1") (pin "3") (pinfunction "E_3") (pintype "passive"))
      (node (ref "T2") (pin "3") (pinfunction "E_3") (pintype "passive"))
    )
    (net (code "35") (name "Net-(T2-B)") (class "Default")
      (node (ref "R2") (pin "2") (pinfunction "2_2") (pintype "passive"))
      (node (ref "R4") (pin "2") (pinfunction "2_2") (pintype "passive"))
      (node (ref "T2") (pin "2") (pinfunction "B_2") (pintype "passive"))
    )
    (net (code "36") (name "Net-(T3-B)") (class "Default")
      (node (ref "R7") (pin "1") (pinfunction "1_1") (pintype "passive"))
      (node (ref "T3") (pin "2") (pinfunction "B_2") (pintype "passive"))
    )
    (net (code "37") (name "Net-(T3-E)") (class "Default")
      (node (ref "R5") (pin "2") (pinfunction "2_2") (pintype "passive"))
      (node (ref "T3") (pin "3") (pinfunction "E_3") (pintype "passive"))
      (node (ref "T4") (pin "3") (pinfunction "E_3") (pintype "passive"))
    )
    (net (code "38") (name "Net-(T4-B)") (class "Default")
      (node (ref "R6") (pin "2") (pinfunction "2_2") (pintype "passive"))
      (node (ref "R8") (pin "2") (pinfunction "2_2") (pintype "passive"))
      (node (ref "T4") (pin "2") (pinfunction "B_2") (pintype "passive"))
    )
    (net (code "39") (name "Net-(T5-B)") (class "Default")
      (node (ref "R20") (pin "1") (pinfunction "1_1") (pintype "passive"))
      (node (ref "T5") (pin "2") (pinfunction "B_2") (pintype "passive"))
    )
    (net (code "40") (name "Net-(T5-E)") (class "Default")
      (node (ref "C15") (pin "-") (pinfunction "-_-") (pintype "passive"))
      (node (ref "C20") (pin "-") (pinfunction "-_-") (pintype "passive"))
      (node (ref "R18") (pin "2") (pinfunction "2_2") (pintype "passive"))
      (node (ref "R26") (pin "1") (pinfunction "1_1") (pintype "passive"))
      (node (ref "T5") (pin "3") (pinfunction "E_3") (pintype "passive"))
      (node (ref "TP_VCONT") (pin "1") (pinfunction "1_1") (pintype "passive"))
    )
    (net (code "41") (name "V+") (class "Default")
      (node (ref "C24") (pin "1") (pinfunction "1_1") (pintype "passive"))
      (node (ref "C25") (pin "+") (pinfunction "+_+") (pintype "passive"))
      (node (ref "C26") (pin "2") (pinfunction "2_2") (pintype "passive"))
      (node (ref "IC1") (pin "8") (pinfunction "V+_8") (pintype "power_in"))
      (node (ref "IC2") (pin "8") (pinfunction "V+_8") (pintype "power_in"))
      (node (ref "LM2917_5") (pin "1") (pinfunction "1_1") (pintype "passive"))
      (node (ref "R16") (pin "2") (pinfunction "2_2") (pintype "passive"))
      (node (ref "R19") (pin "2") (pinfunction "2_2") (pintype "passive"))
      (node (ref "R21") (pin "2") (pinfunction "2_2") (pintype "passive"))
      (node (ref "R29") (pin "E") (pinfunction "E_E") (pintype "passive"))
      (node (ref "R35") (pin "1") (pinfunction "1_1") (pintype "passive"))
      (node (ref "S_JACK") (pin "3") (pinfunction "3_3") (pintype "passive"))
    )
    (net (code "42") (name "V-") (class "Default")
      (node (ref "C21") (pin "2") (pinfunction "2_2") (pintype "passive"))
      (node (ref "C22") (pin "-") (pinfunction "-_-") (pintype "passive"))
      (node (ref "C25") (pin "-") (pinfunction "-_-") (pintype "passive"))
      (node (ref "C26") (pin "1") (pinfunction "1_1") (pintype "passive"))
      (node (ref "C27") (pin "-") (pinfunction "-_-") (pintype "passive"))
      (node (ref "C32") (pin "2") (pinfunction "2_2") (pintype "passive"))
      (node (ref "IC1") (pin "4") (pinfunction "V-_4") (pintype "power_in"))
      (node (ref "IC2") (pin "4") (pinfunction "V-_4") (pintype "power_in"))
      (node (ref "LM2917_8") (pin "1") (pinfunction "1_1") (pintype "passive"))
      (node (ref "R17") (pin "1") (pinfunction "1_1") (pintype "passive"))
      (node (ref "R22") (pin "2") (pinfunction "2_2") (pintype "passive"))
      (node (ref "R31") (pin "1") (pinfunction "1_1") (pintype "passive"))
      (node (ref "R32") (pin "1") (pinfunction "1_1") (pintype "passive"))
      (node (ref "R33") (pin "1") (pinfunction "1_1") (pintype "passive"))
      (node (ref "R38") (pin "1") (pinfunction "1_1") (pintype "passive"))
      (node (ref "S_JACK") (pin "2") (pinfunction "2_2") (pintype "passive"))
    )
    (net (code "43") (name "unconnected-(S_JACK-Pad4)") (class "Default")
      (node (ref "S_JACK") (pin "4") (pinfunction "4_4") (pintype "passive"))
    )
  )
)
